# legatus_v0_21.net
KiCad netlist of a schematic drawn in EAGLE
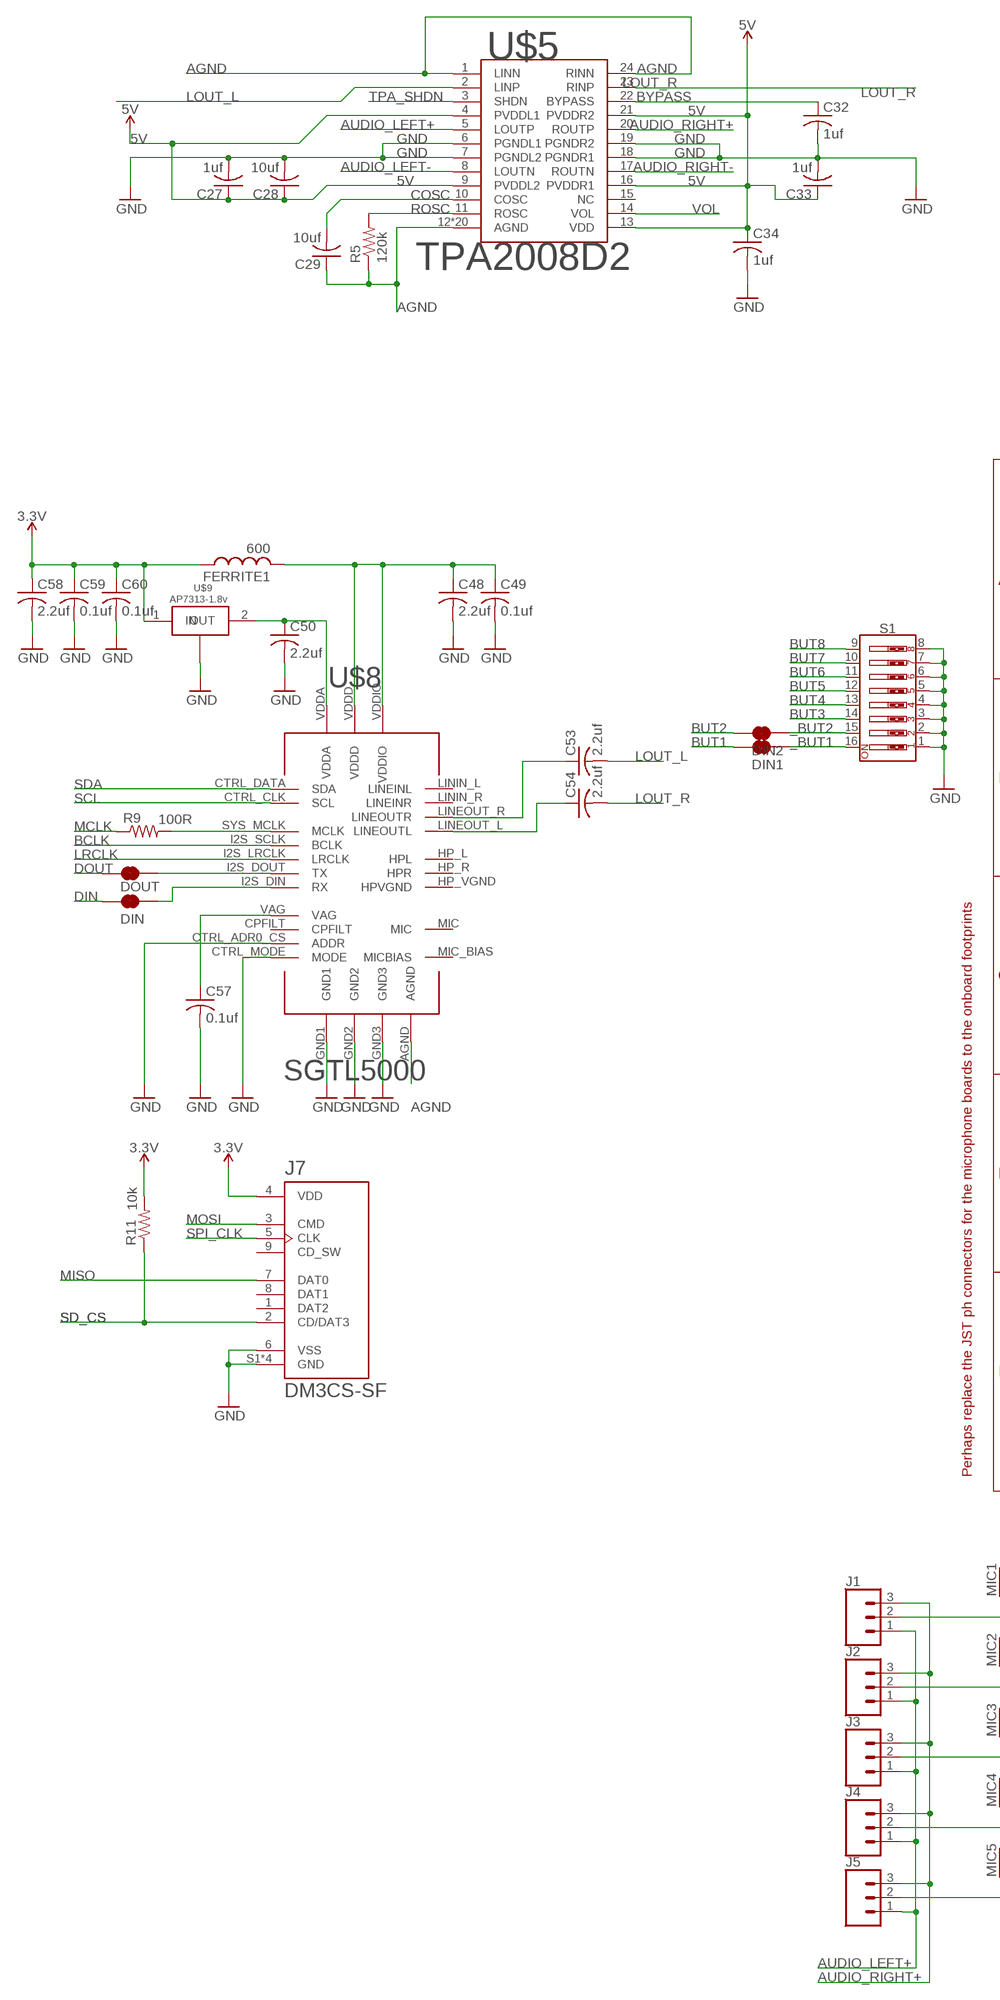
[diagram p0: schematic, sheet 1, part 1 of 2]
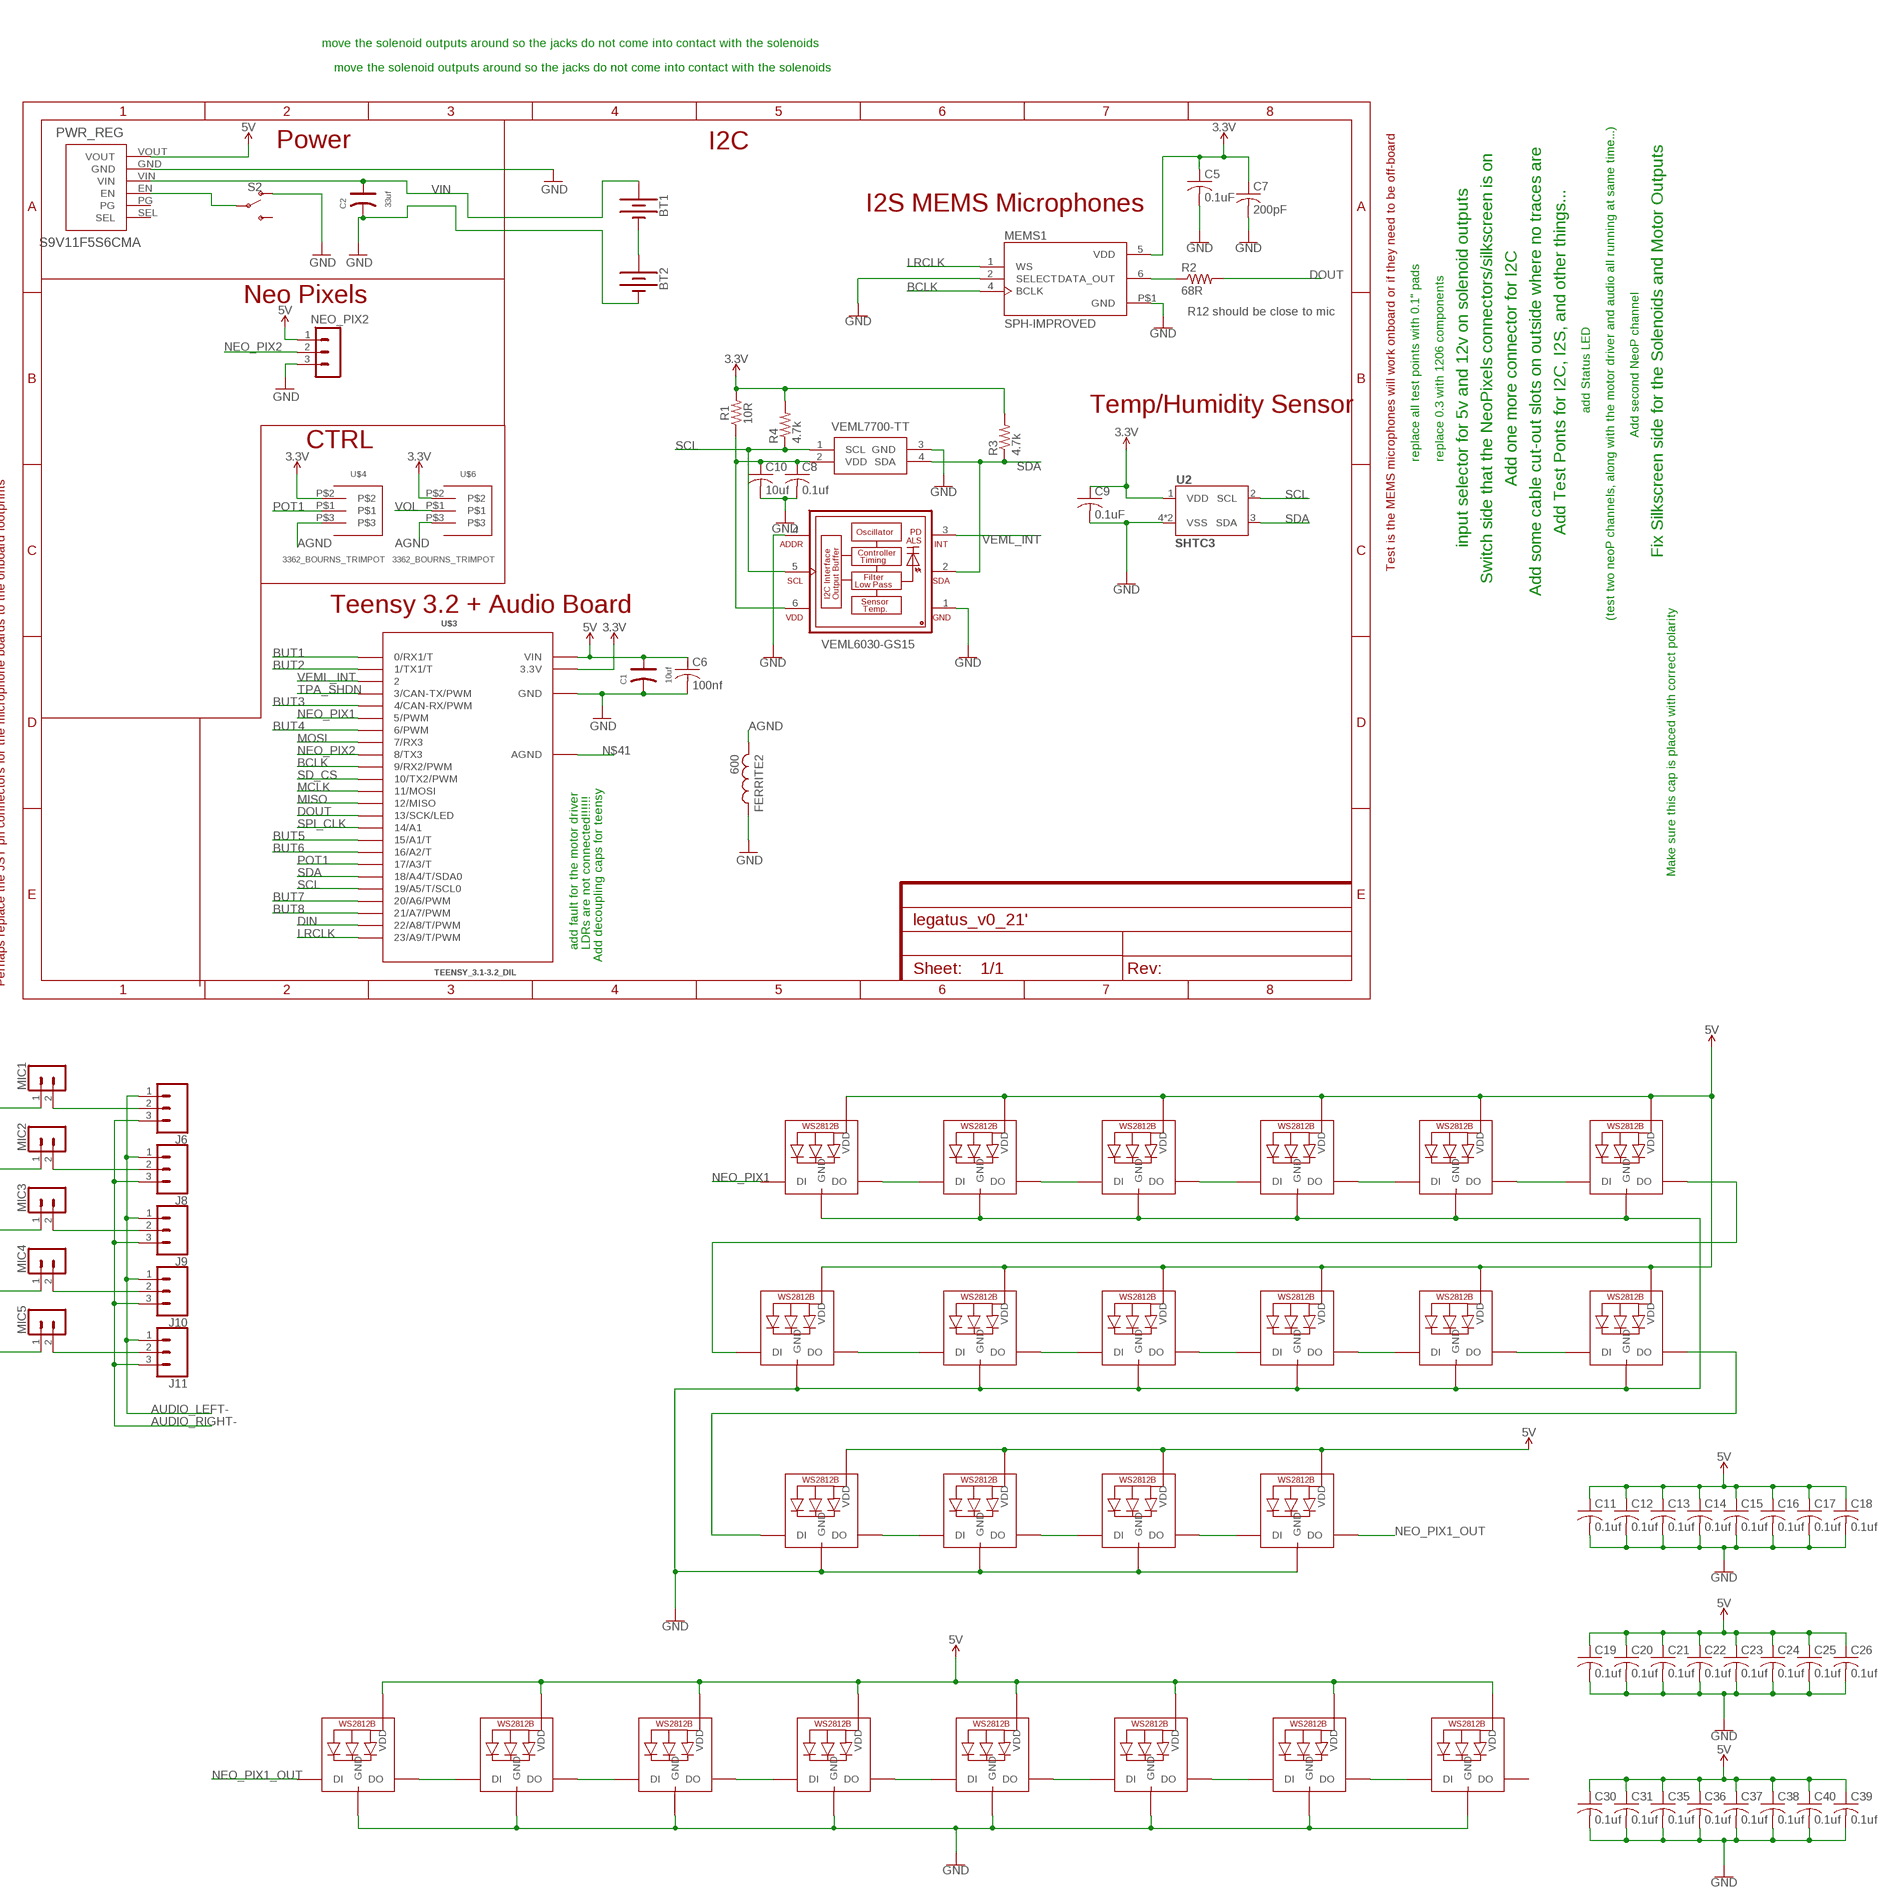
[diagram p1: schematic, sheet 1, part 2 of 2]

(export (version "E")
  (design (tool "Eeschema 10.0.6"))
  (components
    (comp (ref "BT1")
      (value "BATTERY-18650")
      (footprint "eagle-import:BATTERY_18650-HOLDER")
      (libsource (lib "eagle-import") (part "BATTERY-18650"))
    )
    (comp (ref "BT2")
      (value "BATTERY-18650")
      (footprint "eagle-import:BATTERY_18650-HOLDER")
      (libsource (lib "eagle-import") (part "BATTERY-18650"))
    )
    (comp (ref "C1")
      (value "10uf")
      (footprint "eagle-import:PC-D5.3MM")
      (fields (field (name "MPN") "KS 100uF/16V"))
      (libsource (lib "eagle-import") (part "DIP-ALUMINUM-47UF-16V(D5-H7MM)"))
    )
    (comp (ref "C2")
      (value "33uf")
      (footprint "eagle-import:PC-D5.3MM")
      (fields (field (name "MPN") "KS 100uF/16V"))
      (libsource (lib "eagle-import") (part "DIP-ALUMINUM-47UF-16V(D5-H7MM)"))
    )
    (comp (ref "C5")
      (value "0.1uF")
      (footprint "eagle-import:C0805")
      (libsource (lib "eagle-import") (part "rcl_334_C-USC0805"))
    )
    (comp (ref "C6")
      (value "100nf")
      (footprint "eagle-import:C2012")
      (libsource (lib "eagle-import") (part "C-USC2012"))
    )
    (comp (ref "C7")
      (value "200pF")
      (footprint "eagle-import:C0805")
      (libsource (lib "eagle-import") (part "rcl_334_C-USC0805"))
    )
    (comp (ref "C8")
      (value "0.1uf")
      (footprint "eagle-import:C0805")
      (libsource (lib "eagle-import") (part "rcl_334_C-USC0805"))
    )
    (comp (ref "C9")
      (value "0.1uF")
      (footprint "eagle-import:C0805")
      (libsource (lib "eagle-import") (part "rcl_334_C-USC0805"))
    )
    (comp (ref "C10")
      (value "10uf")
      (footprint "eagle-import:C0805")
      (libsource (lib "eagle-import") (part "rcl_334_C-USC0805"))
    )
    (comp (ref "C11")
      (value "0.1uf")
      (footprint "eagle-import:C0805")
      (libsource (lib "eagle-import") (part "rcl_334_C-USC0805"))
    )
    (comp (ref "C12")
      (value "0.1uf")
      (footprint "eagle-import:C0805")
      (libsource (lib "eagle-import") (part "rcl_334_C-USC0805"))
    )
    (comp (ref "C13")
      (value "0.1uf")
      (footprint "eagle-import:C0805")
      (libsource (lib "eagle-import") (part "rcl_334_C-USC0805"))
    )
    (comp (ref "C14")
      (value "0.1uf")
      (footprint "eagle-import:C0805")
      (libsource (lib "eagle-import") (part "rcl_334_C-USC0805"))
    )
    (comp (ref "C15")
      (value "0.1uf")
      (footprint "eagle-import:C0805")
      (libsource (lib "eagle-import") (part "rcl_334_C-USC0805"))
    )
    (comp (ref "C16")
      (value "0.1uf")
      (footprint "eagle-import:C0805")
      (libsource (lib "eagle-import") (part "rcl_334_C-USC0805"))
    )
    (comp (ref "C17")
      (value "0.1uf")
      (footprint "eagle-import:C0805")
      (libsource (lib "eagle-import") (part "rcl_334_C-USC0805"))
    )
    (comp (ref "C18")
      (value "0.1uf")
      (footprint "eagle-import:C0805")
      (libsource (lib "eagle-import") (part "rcl_334_C-USC0805"))
    )
    (comp (ref "C19")
      (value "0.1uf")
      (footprint "eagle-import:C0805")
      (libsource (lib "eagle-import") (part "rcl_334_C-USC0805"))
    )
    (comp (ref "C20")
      (value "0.1uf")
      (footprint "eagle-import:C0805")
      (libsource (lib "eagle-import") (part "rcl_334_C-USC0805"))
    )
    (comp (ref "C21")
      (value "0.1uf")
      (footprint "eagle-import:C0805")
      (libsource (lib "eagle-import") (part "rcl_334_C-USC0805"))
    )
    (comp (ref "C22")
      (value "0.1uf")
      (footprint "eagle-import:C0805")
      (libsource (lib "eagle-import") (part "rcl_334_C-USC0805"))
    )
    (comp (ref "C23")
      (value "0.1uf")
      (footprint "eagle-import:C0805")
      (libsource (lib "eagle-import") (part "rcl_334_C-USC0805"))
    )
    (comp (ref "C24")
      (value "0.1uf")
      (footprint "eagle-import:C0805")
      (libsource (lib "eagle-import") (part "rcl_334_C-USC0805"))
    )
    (comp (ref "C25")
      (value "0.1uf")
      (footprint "eagle-import:C0805")
      (libsource (lib "eagle-import") (part "rcl_334_C-USC0805"))
    )
    (comp (ref "C26")
      (value "0.1uf")
      (footprint "eagle-import:C0805")
      (libsource (lib "eagle-import") (part "rcl_334_C-USC0805"))
    )
    (comp (ref "C27")
      (value "1uf")
      (footprint "eagle-import:C0805")
      (libsource (lib "eagle-import") (part "rcl_334_C-USC0805"))
    )
    (comp (ref "C28")
      (value "10uf")
      (footprint "eagle-import:C0805")
      (libsource (lib "eagle-import") (part "rcl_334_C-USC0805"))
    )
    (comp (ref "C29")
      (value "10uf")
      (footprint "eagle-import:C0805")
      (libsource (lib "eagle-import") (part "rcl_334_C-USC0805"))
    )
    (comp (ref "C30")
      (value "0.1uf")
      (footprint "eagle-import:C0805")
      (libsource (lib "eagle-import") (part "rcl_334_C-USC0805"))
    )
    (comp (ref "C31")
      (value "0.1uf")
      (footprint "eagle-import:C0805")
      (libsource (lib "eagle-import") (part "rcl_334_C-USC0805"))
    )
    (comp (ref "C32")
      (value "1uf")
      (footprint "eagle-import:C0805")
      (libsource (lib "eagle-import") (part "rcl_334_C-USC0805"))
    )
    (comp (ref "C33")
      (value "1uf")
      (footprint "eagle-import:C0805")
      (libsource (lib "eagle-import") (part "rcl_334_C-USC0805"))
    )
    (comp (ref "C34")
      (value "1uf")
      (footprint "eagle-import:C0805")
      (libsource (lib "eagle-import") (part "rcl_334_C-USC0805"))
    )
    (comp (ref "C35")
      (value "0.1uf")
      (footprint "eagle-import:C0805")
      (libsource (lib "eagle-import") (part "rcl_334_C-USC0805"))
    )
    (comp (ref "C36")
      (value "0.1uf")
      (footprint "eagle-import:C0805")
      (libsource (lib "eagle-import") (part "rcl_334_C-USC0805"))
    )
    (comp (ref "C37")
      (value "0.1uf")
      (footprint "eagle-import:C0805")
      (libsource (lib "eagle-import") (part "rcl_334_C-USC0805"))
    )
    (comp (ref "C38")
      (value "0.1uf")
      (footprint "eagle-import:C0805")
      (libsource (lib "eagle-import") (part "rcl_334_C-USC0805"))
    )
    (comp (ref "C39")
      (value "0.1uf")
      (footprint "eagle-import:C0805")
      (libsource (lib "eagle-import") (part "rcl_334_C-USC0805"))
    )
    (comp (ref "C40")
      (value "0.1uf")
      (footprint "eagle-import:C0805")
      (libsource (lib "eagle-import") (part "rcl_334_C-USC0805"))
    )
    (comp (ref "C48")
      (value "2.2uf")
      (footprint "eagle-import:C0805")
      (libsource (lib "eagle-import") (part "rcl_334_C-USC0805"))
    )
    (comp (ref "C49")
      (value "0.1uf")
      (footprint "eagle-import:C0805")
      (libsource (lib "eagle-import") (part "rcl_334_C-USC0805"))
    )
    (comp (ref "C50")
      (value "2.2uf")
      (footprint "eagle-import:C0805")
      (libsource (lib "eagle-import") (part "rcl_334_C-USC0805"))
    )
    (comp (ref "C53")
      (value "2.2uf")
      (footprint "eagle-import:C0805")
      (libsource (lib "eagle-import") (part "rcl_334_C-USC0805"))
    )
    (comp (ref "C54")
      (value "2.2uf")
      (footprint "eagle-import:C0805")
      (libsource (lib "eagle-import") (part "rcl_334_C-USC0805"))
    )
    (comp (ref "C57")
      (value "0.1uf")
      (footprint "eagle-import:C0805")
      (libsource (lib "eagle-import") (part "rcl_334_C-USC0805"))
    )
    (comp (ref "C58")
      (value "2.2uf")
      (footprint "eagle-import:C0805")
      (libsource (lib "eagle-import") (part "rcl_334_C-USC0805"))
    )
    (comp (ref "C59")
      (value "0.1uf")
      (footprint "eagle-import:C0805")
      (libsource (lib "eagle-import") (part "rcl_334_C-USC0805"))
    )
    (comp (ref "C60")
      (value "0.1uf")
      (footprint "eagle-import:C0805")
      (libsource (lib "eagle-import") (part "rcl_334_C-USC0805"))
    )
    (comp (ref "DIN")
      (value "JUMPER-SMT_2_NC_TRACE_SILK")
      (footprint "eagle-import:SMT-JUMPER_2_NC_TRACE_SILK")
      (libsource (lib "eagle-import") (part "JUMPER-SMT_2_NC_TRACE_SILK"))
    )
    (comp (ref "DIN1")
      (value "JUMPER-SMT_2_NC_TRACE_SILK")
      (footprint "eagle-import:SMT-JUMPER_2_NC_TRACE_SILK")
      (libsource (lib "eagle-import") (part "JUMPER-SMT_2_NC_TRACE_SILK"))
    )
    (comp (ref "DIN2")
      (value "JUMPER-SMT_2_NC_TRACE_SILK")
      (footprint "eagle-import:SMT-JUMPER_2_NC_TRACE_SILK")
      (libsource (lib "eagle-import") (part "JUMPER-SMT_2_NC_TRACE_SILK"))
    )
    (comp (ref "DOUT")
      (value "JUMPER-SMT_2_NC_TRACE_SILK")
      (footprint "eagle-import:SMT-JUMPER_2_NC_TRACE_SILK")
      (libsource (lib "eagle-import") (part "JUMPER-SMT_2_NC_TRACE_SILK"))
    )
    (comp (ref "FERRITE1")
      (value "600")
      (footprint "eagle-import:RESC0805_N")
      (libsource (lib "eagle-import") (part "INDUCTOR_0805_N"))
    )
    (comp (ref "FERRITE2")
      (value "600")
      (footprint "eagle-import:RESC0805_N")
      (libsource (lib "eagle-import") (part "INDUCTOR_0805_N"))
    )
    (comp (ref "J1")
      (value "CONN_03")
      (footprint "eagle-import:1X03")
      (libsource (lib "eagle-import") (part "CONN_03"))
    )
    (comp (ref "J2")
      (value "CONN_03")
      (footprint "eagle-import:1X03")
      (libsource (lib "eagle-import") (part "CONN_03"))
    )
    (comp (ref "J3")
      (value "CONN_03")
      (footprint "eagle-import:1X03")
      (libsource (lib "eagle-import") (part "CONN_03"))
    )
    (comp (ref "J4")
      (value "CONN_03")
      (footprint "eagle-import:1X03")
      (libsource (lib "eagle-import") (part "CONN_03"))
    )
    (comp (ref "J5")
      (value "CONN_03")
      (footprint "eagle-import:1X03")
      (libsource (lib "eagle-import") (part "CONN_03"))
    )
    (comp (ref "J6")
      (value "CONN_03")
      (footprint "eagle-import:1X03")
      (libsource (lib "eagle-import") (part "CONN_03"))
    )
    (comp (ref "J7")
      (value "DM3CS-SF")
      (footprint "eagle-import:HRS_DM3CS-SF")
      (fields (field (name "MF") "Hirose"))
      (libsource (lib "eagle-import") (part "DM3CS-SF"))
    )
    (comp (ref "J8")
      (value "CONN_03")
      (footprint "eagle-import:1X03")
      (libsource (lib "eagle-import") (part "CONN_03"))
    )
    (comp (ref "J9")
      (value "CONN_03")
      (footprint "eagle-import:1X03")
      (libsource (lib "eagle-import") (part "CONN_03"))
    )
    (comp (ref "J10")
      (value "CONN_03")
      (footprint "eagle-import:1X03")
      (libsource (lib "eagle-import") (part "CONN_03"))
    )
    (comp (ref "J11")
      (value "CONN_03")
      (footprint "eagle-import:1X03")
      (libsource (lib "eagle-import") (part "CONN_03"))
    )
    (comp (ref "LED1")
      (value "WS2812B_5050N")
      (footprint "eagle-import:WS2812B-NARROW")
      (libsource (lib "eagle-import") (part "WS2812B_5050N"))
    )
    (comp (ref "LED2")
      (value "WS2812B_5050N")
      (footprint "eagle-import:WS2812B-NARROW")
      (libsource (lib "eagle-import") (part "WS2812B_5050N"))
    )
    (comp (ref "LED3")
      (value "WS2812B_5050N")
      (footprint "eagle-import:WS2812B-NARROW")
      (libsource (lib "eagle-import") (part "WS2812B_5050N"))
    )
    (comp (ref "LED4")
      (value "WS2812B_5050N")
      (footprint "eagle-import:WS2812B-NARROW")
      (libsource (lib "eagle-import") (part "WS2812B_5050N"))
    )
    (comp (ref "LED5")
      (value "WS2812B_5050N")
      (footprint "eagle-import:WS2812B-NARROW")
      (libsource (lib "eagle-import") (part "WS2812B_5050N"))
    )
    (comp (ref "LED6")
      (value "WS2812B_5050N")
      (footprint "eagle-import:WS2812B-NARROW")
      (libsource (lib "eagle-import") (part "WS2812B_5050N"))
    )
    (comp (ref "LED7")
      (value "WS2812B_5050N")
      (footprint "eagle-import:WS2812B-NARROW")
      (libsource (lib "eagle-import") (part "WS2812B_5050N"))
    )
    (comp (ref "LED8")
      (value "WS2812B_5050N")
      (footprint "eagle-import:WS2812B-NARROW")
      (libsource (lib "eagle-import") (part "WS2812B_5050N"))
    )
    (comp (ref "LED9")
      (value "WS2812B_5050N")
      (footprint "eagle-import:WS2812B-NARROW")
      (libsource (lib "eagle-import") (part "WS2812B_5050N"))
    )
    (comp (ref "LED10")
      (value "WS2812B_5050N")
      (footprint "eagle-import:WS2812B-NARROW")
      (libsource (lib "eagle-import") (part "WS2812B_5050N"))
    )
    (comp (ref "LED11")
      (value "WS2812B_5050N")
      (footprint "eagle-import:WS2812B-NARROW")
      (libsource (lib "eagle-import") (part "WS2812B_5050N"))
    )
    (comp (ref "LED12")
      (value "WS2812B_5050N")
      (footprint "eagle-import:WS2812B-NARROW")
      (libsource (lib "eagle-import") (part "WS2812B_5050N"))
    )
    (comp (ref "LED13")
      (value "WS2812B_5050N")
      (footprint "eagle-import:WS2812B-NARROW")
      (libsource (lib "eagle-import") (part "WS2812B_5050N"))
    )
    (comp (ref "LED14")
      (value "WS2812B_5050N")
      (footprint "eagle-import:WS2812B-NARROW")
      (libsource (lib "eagle-import") (part "WS2812B_5050N"))
    )
    (comp (ref "LED15")
      (value "WS2812B_5050N")
      (footprint "eagle-import:WS2812B-NARROW")
      (libsource (lib "eagle-import") (part "WS2812B_5050N"))
    )
    (comp (ref "LED16")
      (value "WS2812B_5050N")
      (footprint "eagle-import:WS2812B-NARROW")
      (libsource (lib "eagle-import") (part "WS2812B_5050N"))
    )
    (comp (ref "LED17")
      (value "WS2812B_5050N")
      (footprint "eagle-import:WS2812B-NARROW")
      (libsource (lib "eagle-import") (part "WS2812B_5050N"))
    )
    (comp (ref "LED18")
      (value "WS2812B_5050N")
      (footprint "eagle-import:WS2812B-NARROW")
      (libsource (lib "eagle-import") (part "WS2812B_5050N"))
    )
    (comp (ref "LED19")
      (value "WS2812B_5050N")
      (footprint "eagle-import:WS2812B-NARROW")
      (libsource (lib "eagle-import") (part "WS2812B_5050N"))
    )
    (comp (ref "LED20")
      (value "WS2812B_5050N")
      (footprint "eagle-import:WS2812B-NARROW")
      (libsource (lib "eagle-import") (part "WS2812B_5050N"))
    )
    (comp (ref "LED21")
      (value "WS2812B_5050N")
      (footprint "eagle-import:WS2812B-NARROW")
      (libsource (lib "eagle-import") (part "WS2812B_5050N"))
    )
    (comp (ref "LED22")
      (value "WS2812B_5050N")
      (footprint "eagle-import:WS2812B-NARROW")
      (libsource (lib "eagle-import") (part "WS2812B_5050N"))
    )
    (comp (ref "LED23")
      (value "WS2812B_5050N")
      (footprint "eagle-import:WS2812B-NARROW")
      (libsource (lib "eagle-import") (part "WS2812B_5050N"))
    )
    (comp (ref "LED24")
      (value "WS2812B_5050N")
      (footprint "eagle-import:WS2812B-NARROW")
      (libsource (lib "eagle-import") (part "WS2812B_5050N"))
    )
    (comp (ref "MEMS1")
      (value "SPH-IMPROVED")
      (footprint "eagle-import:MIC_SPH0645LM4H-B_LARGER_RING")
      (libsource (lib "eagle-import") (part "SPH-IMPROVED"))
    )
    (comp (ref "MIC1")
      (value "B2B-PH-K")
      (footprint "eagle-import:B2B-PH-K")
      (libsource (lib "eagle-import") (part "B2B-PH-K"))
    )
    (comp (ref "MIC2")
      (value "B2B-PH-K")
      (footprint "eagle-import:B2B-PH-K")
      (libsource (lib "eagle-import") (part "B2B-PH-K"))
    )
    (comp (ref "MIC3")
      (value "B2B-PH-K")
      (footprint "eagle-import:B2B-PH-K")
      (libsource (lib "eagle-import") (part "B2B-PH-K"))
    )
    (comp (ref "MIC4")
      (value "B2B-PH-K")
      (footprint "eagle-import:B2B-PH-K")
      (libsource (lib "eagle-import") (part "B2B-PH-K"))
    )
    (comp (ref "MIC5")
      (value "B2B-PH-K")
      (footprint "eagle-import:B2B-PH-K")
      (libsource (lib "eagle-import") (part "B2B-PH-K"))
    )
    (comp (ref "NEO_PIX2")
      (value "B3B-PH-K")
      (footprint "eagle-import:B3B-PH-K")
      (libsource (lib "eagle-import") (part "B3B-PH-K"))
    )
    (comp (ref "PWR_REG")
      (value "S9V11F5S6CMA")
      (footprint "eagle-import:S9V11F3S5CMA")
      (libsource (lib "eagle-import") (part "S9V11F5S6CMA"))
    )
    (comp (ref "R1")
      (value "10R")
      (footprint "eagle-import:R0805")
      (libsource (lib "eagle-import") (part "audio amplifier example_970892_R-US_R0805"))
    )
    (comp (ref "R2")
      (value "68R")
      (footprint "eagle-import:M0805")
      (libsource (lib "eagle-import") (part "R-US_M0805"))
    )
    (comp (ref "R3")
      (value "4.7k")
      (footprint "eagle-import:M0805")
      (libsource (lib "eagle-import") (part "R-US_M0805"))
    )
    (comp (ref "R4")
      (value "4.7k")
      (footprint "eagle-import:M0805")
      (libsource (lib "eagle-import") (part "R-US_M0805"))
    )
    (comp (ref "R5")
      (value "120k")
      (footprint "eagle-import:M0805")
      (libsource (lib "eagle-import") (part "R-US_M0805"))
    )
    (comp (ref "R9")
      (value "100R")
      (footprint "eagle-import:M0805")
      (libsource (lib "eagle-import") (part "rcl_R-US_M0805"))
    )
    (comp (ref "R11")
      (value "10k")
      (footprint "eagle-import:M0805")
      (libsource (lib "eagle-import") (part "rcl_R-US_M0805"))
    )
    (comp (ref "S1")
      (value "DIP-08-PTH")
      (footprint "eagle-import:DIPSWITCH-08")
      (libsource (lib "eagle-import") (part "DIP-08-PTH"))
    )
    (comp (ref "S2")
      (value "SWITCH-SPDT-PTH-11.6X4.0MM-LOCK")
      (footprint "eagle-import:SWITCH_SPDT_PTH_11.6X4.0MM_LOCK")
      (libsource (lib "eagle-import") (part "SWITCH-SPDT-PTH-11.6X4.0MM-LOCK"))
    )
    (comp (ref "U$3")
      (value "TEENSY_3.1-3.2_DIL")
      (footprint "eagle-import:TEENSY_3.0-3.2&LC_DIL")
      (libsource (lib "eagle-import") (part "TEENSY_3.1-3.2_DIL"))
    )
    (comp (ref "U$4")
      (value "3362_BOURNS_TRIMPOT")
      (footprint "eagle-import:3362_BOURNS_TRIMPOT")
      (libsource (lib "eagle-import") (part "3362_BOURNS_TRIMPOT"))
    )
    (comp (ref "U$5")
      (value "TPA2008D2")
      (footprint "eagle-import:PWP-TSSOP24")
      (libsource (lib "eagle-import") (part "TPA2008D2"))
    )
    (comp (ref "U$6")
      (value "3362_BOURNS_TRIMPOT")
      (footprint "eagle-import:3362_BOURNS_TRIMPOT")
      (libsource (lib "eagle-import") (part "3362_BOURNS_TRIMPOT"))
    )
    (comp (ref "U$8")
      (value "SGTL5000")
      (footprint "eagle-import:QFN-32-5X5MM")
      (libsource (lib "eagle-import") (part "SGTL5000"))
    )
    (comp (ref "U$9")
      (value "AP7313-1.8v")
      (footprint "eagle-import:SOT-23")
      (libsource (lib "eagle-import") (part "AP7313"))
    )
    (comp (ref "U2")
      (value "SHTC3")
      (footprint "eagle-import:SHTC3")
      (libsource (lib "eagle-import") (part "SHTC3"))
    )
    (comp (ref "VEML1")
      (value "VEML7700-TT")
      (footprint "eagle-import:VEML7700")
      (fields (field (name "MOUSER_PART_NUMBER") "78-VEML7700-TT") (field (name "RS_PART_NUMBER") "1226791P"))
      (libsource (lib "eagle-import") (part "VEML7700-TT"))
    )
    (comp (ref "VMEL1")
      (value "VEML6030-GS15")
      (footprint "eagle-import:VISHAY_VEML6030_2X2X0.87")
      (fields (field (name "MF") "Vishay Semiconductor"))
      (libsource (lib "eagle-import") (part "VEML6030-GS15"))
    )
  )
  (nets
    (net (code "1") (name "/AGND") (class "Default")
      (node (ref "C29") (pin "1") (pinfunction "1_1") (pintype "passive"))
      (node (ref "FERRITE2") (pin "2") (pinfunction "2_2") (pintype "passive"))
      (node (ref "R5") (pin "1") (pinfunction "1_1") (pintype "passive"))
      (node (ref "U$4") (pin "P$3") (pinfunction "P$3_P$3") (pintype "bidirectional"))
      (node (ref "U$5") (pin "1") (pinfunction "LINN_1") (pintype "bidirectional"))
      (node (ref "U$5") (pin "12") (pinfunction "AGND_12") (pintype "bidirectional"))
      (node (ref "U$5") (pin "24") (pinfunction "RINN_24") (pintype "bidirectional"))
      (node (ref "U$5") (pin "EXP") (pinfunction "AGND_EXP") (pintype "bidirectional"))
      (node (ref "U$5") (pin "EXP@1") (pinfunction "AGND_EXP@1") (pintype "bidirectional"))
      (node (ref "U$5") (pin "EXP@10") (pinfunction "AGND_EXP@10") (pintype "bidirectional"))
      (node (ref "U$5") (pin "EXP@11") (pinfunction "AGND_EXP@11") (pintype "bidirectional"))
      (node (ref "U$5") (pin "EXP@12") (pinfunction "AGND_EXP@12") (pintype "bidirectional"))
      (node (ref "U$5") (pin "EXP@13") (pinfunction "AGND_EXP@13") (pintype "bidirectional"))
      (node (ref "U$5") (pin "EXP@14") (pinfunction "AGND_EXP@14") (pintype "bidirectional"))
      (node (ref "U$5") (pin "EXP@15") (pinfunction "AGND_EXP@15") (pintype "bidirectional"))
      (node (ref "U$5") (pin "EXP@16") (pinfunction "AGND_EXP@16") (pintype "bidirectional"))
      (node (ref "U$5") (pin "EXP@17") (pinfunction "AGND_EXP@17") (pintype "bidirectional"))
      (node (ref "U$5") (pin "EXP@18") (pinfunction "AGND_EXP@18") (pintype "bidirectional"))
      (node (ref "U$5") (pin "EXP@2") (pinfunction "AGND_EXP@2") (pintype "bidirectional"))
      (node (ref "U$5") (pin "EXP@3") (pinfunction "AGND_EXP@3") (pintype "bidirectional"))
      (node (ref "U$5") (pin "EXP@4") (pinfunction "AGND_EXP@4") (pintype "bidirectional"))
      (node (ref "U$5") (pin "EXP@5") (pinfunction "AGND_EXP@5") (pintype "bidirectional"))
      (node (ref "U$5") (pin "EXP@6") (pinfunction "AGND_EXP@6") (pintype "bidirectional"))
      (node (ref "U$5") (pin "EXP@7") (pinfunction "AGND_EXP@7") (pintype "bidirectional"))
      (node (ref "U$5") (pin "EXP@8") (pinfunction "AGND_EXP@8") (pintype "bidirectional"))
      (node (ref "U$5") (pin "EXP@9") (pinfunction "AGND_EXP@9") (pintype "bidirectional"))
      (node (ref "U$6") (pin "P$3") (pinfunction "P$3_P$3") (pintype "bidirectional"))
      (node (ref "U$8") (pin "AGND") (pinfunction "AGND_AGND") (pintype "bidirectional"))
    )
    (net (code "2") (name "/AUDIO_LEFT+") (class "Default")
      (node (ref "J1") (pin "1") (pinfunction "1_1") (pintype "passive"))
      (node (ref "J2") (pin "1") (pinfunction "1_1") (pintype "passive"))
      (node (ref "J3") (pin "1") (pinfunction "1_1") (pintype "passive"))
      (node (ref "J4") (pin "1") (pinfunction "1_1") (pintype "passive"))
      (node (ref "J5") (pin "1") (pinfunction "1_1") (pintype "passive"))
      (node (ref "U$5") (pin "5") (pinfunction "LOUTP_5") (pintype "bidirectional"))
    )
    (net (code "3") (name "/AUDIO_LEFT-") (class "Default")
      (node (ref "J10") (pin "1") (pinfunction "1_1") (pintype "passive"))
      (node (ref "J11") (pin "1") (pinfunction "1_1") (pintype "passive"))
      (node (ref "J6") (pin "1") (pinfunction "1_1") (pintype "passive"))
      (node (ref "J8") (pin "1") (pinfunction "1_1") (pintype "passive"))
      (node (ref "J9") (pin "1") (pinfunction "1_1") (pintype "passive"))
      (node (ref "U$5") (pin "8") (pinfunction "LOUTN_8") (pintype "bidirectional"))
    )
    (net (code "4") (name "/AUDIO_RIGHT+") (class "Default")
      (node (ref "J1") (pin "3") (pinfunction "3_3") (pintype "passive"))
      (node (ref "J2") (pin "3") (pinfunction "3_3") (pintype "passive"))
      (node (ref "J3") (pin "3") (pinfunction "3_3") (pintype "passive"))
      (node (ref "J4") (pin "3") (pinfunction "3_3") (pintype "passive"))
      (node (ref "J5") (pin "3") (pinfunction "3_3") (pintype "passive"))
      (node (ref "U$5") (pin "20") (pinfunction "ROUTP_20") (pintype "bidirectional"))
    )
    (net (code "5") (name "/AUDIO_RIGHT-") (class "Default")
      (node (ref "J10") (pin "3") (pinfunction "3_3") (pintype "passive"))
      (node (ref "J11") (pin "3") (pinfunction "3_3") (pintype "passive"))
      (node (ref "J6") (pin "3") (pinfunction "3_3") (pintype "passive"))
      (node (ref "J8") (pin "3") (pinfunction "3_3") (pintype "passive"))
      (node (ref "J9") (pin "3") (pinfunction "3_3") (pintype "passive"))
      (node (ref "U$5") (pin "17") (pinfunction "ROUTN_17") (pintype "bidirectional"))
    )
    (net (code "6") (name "/BCLK") (class "Default")
      (node (ref "MEMS1") (pin "4") (pinfunction "BCLK_4") (pintype "input"))
      (node (ref "U$3") (pin "9") (pinfunction "9/RX2/PWM_9") (pintype "bidirectional"))
      (node (ref "U$8") (pin "I2S_SCLK") (pinfunction "BCLK_I2S_SCLK") (pintype "bidirectional"))
    )
    (net (code "7") (name "/BUT1") (class "Default")
      (node (ref "DIN1") (pin "1") (pinfunction "1_1") (pintype "passive"))
      (node (ref "U$3") (pin "0") (pinfunction "0/RX1/T_0") (pintype "bidirectional"))
    )
    (net (code "8") (name "/BUT2") (class "Default")
      (node (ref "DIN2") (pin "1") (pinfunction "1_1") (pintype "passive"))
      (node (ref "U$3") (pin "1") (pinfunction "1/TX1/T_1") (pintype "bidirectional"))
    )
    (net (code "9") (name "/BUT3") (class "Default")
      (node (ref "S1") (pin "14") (pinfunction "14_14") (pintype "passive"))
      (node (ref "U$3") (pin "4") (pinfunction "4/CAN-RX/PWM_4") (pintype "bidirectional"))
    )
    (net (code "10") (name "/BUT4") (class "Default")
      (node (ref "S1") (pin "13") (pinfunction "13_13") (pintype "passive"))
      (node (ref "U$3") (pin "6") (pinfunction "6/PWM_6") (pintype "bidirectional"))
    )
    (net (code "11") (name "/BUT5") (class "Default")
      (node (ref "S1") (pin "12") (pinfunction "12_12") (pintype "passive"))
      (node (ref "U$3") (pin "15/A1") (pinfunction "15/A1/T_15/A1") (pintype "bidirectional"))
    )
    (net (code "12") (name "/BUT6") (class "Default")
      (node (ref "S1") (pin "11") (pinfunction "11_11") (pintype "passive"))
      (node (ref "U$3") (pin "16/A2") (pinfunction "16/A2/T_16/A2") (pintype "bidirectional"))
    )
    (net (code "13") (name "/BUT7") (class "Default")
      (node (ref "S1") (pin "10") (pinfunction "10_10") (pintype "passive"))
      (node (ref "U$3") (pin "20/A6") (pinfunction "20/A6/PWM_20/A6") (pintype "bidirectional"))
    )
    (net (code "14") (name "/BUT8") (class "Default")
      (node (ref "S1") (pin "9") (pinfunction "9_9") (pintype "passive"))
      (node (ref "U$3") (pin "21/A7") (pinfunction "21/A7/PWM_21/A7") (pintype "bidirectional"))
    )
    (net (code "15") (name "/BYPASS") (class "Default")
      (node (ref "C32") (pin "1") (pinfunction "1_1") (pintype "passive"))
      (node (ref "U$5") (pin "22") (pinfunction "BYPASS_22") (pintype "bidirectional"))
    )
    (net (code "16") (name "/COSC") (class "Default")
      (node (ref "C29") (pin "2") (pinfunction "2_2") (pintype "passive"))
      (node (ref "U$5") (pin "10") (pinfunction "COSC_10") (pintype "bidirectional"))
    )
    (net (code "17") (name "/DIN") (class "Default")
      (node (ref "DIN") (pin "1") (pinfunction "1_1") (pintype "passive"))
      (node (ref "U$3") (pin "22/A8") (pinfunction "22/A8/T/PWM_22/A8") (pintype "bidirectional"))
    )
    (net (code "18") (name "/DOUT") (class "Default")
      (node (ref "DOUT") (pin "1") (pinfunction "1_1") (pintype "passive"))
      (node (ref "R2") (pin "2") (pinfunction "2_2") (pintype "passive"))
      (node (ref "U$3") (pin "13") (pinfunction "13/SCK/LED_13") (pintype "bidirectional"))
    )
    (net (code "19") (name "/LOUT_L") (class "Default")
      (node (ref "C53") (pin "2") (pinfunction "2_2") (pintype "passive"))
      (node (ref "U$5") (pin "2") (pinfunction "LINP_2") (pintype "bidirectional"))
    )
    (net (code "20") (name "/LOUT_R") (class "Default")
      (node (ref "C54") (pin "2") (pinfunction "2_2") (pintype "passive"))
      (node (ref "U$5") (pin "23") (pinfunction "RINP_23") (pintype "bidirectional"))
    )
    (net (code "21") (name "/LRCLK") (class "Default")
      (node (ref "MEMS1") (pin "1") (pinfunction "WS_1") (pintype "input"))
      (node (ref "U$3") (pin "23/A9") (pinfunction "23/A9/T/PWM_23/A9") (pintype "bidirectional"))
      (node (ref "U$8") (pin "I2S_LRCLK") (pinfunction "LRCLK_I2S_LRCLK") (pintype "bidirectional"))
    )
    (net (code "22") (name "/MCLK") (class "Default")
      (node (ref "R9") (pin "1") (pinfunction "1_1") (pintype "passive"))
      (node (ref "U$3") (pin "11") (pinfunction "11/MOSI_11") (pintype "bidirectional"))
    )
    (net (code "23") (name "/MISO") (class "Default")
      (node (ref "J7") (pin "7") (pinfunction "DAT0_7") (pintype "passive"))
      (node (ref "U$3") (pin "12") (pinfunction "12/MISO_12") (pintype "bidirectional"))
    )
    (net (code "24") (name "/MOSI") (class "Default")
      (node (ref "J7") (pin "3") (pinfunction "CMD_3") (pintype "passive"))
      (node (ref "U$3") (pin "7") (pinfunction "7/RX3_7") (pintype "bidirectional"))
    )
    (net (code "25") (name "/N$41") (class "Default")
      (node (ref "U$3") (pin "AGND") (pinfunction "AGND_AGND") (pintype "power_in"))
    )
    (net (code "26") (name "/NEO_PIX1") (class "Default")
      (node (ref "LED1") (pin "4-DIN") (pinfunction "DI_4-DIN") (pintype "input"))
      (node (ref "U$3") (pin "5") (pinfunction "5/PWM_5") (pintype "bidirectional"))
    )
    (net (code "27") (name "/NEO_PIX1_OUT") (class "Default")
      (node (ref "LED16") (pin "2-DOUT") (pinfunction "DO_2-DOUT") (pintype "output"))
      (node (ref "LED17") (pin "4-DIN") (pinfunction "DI_4-DIN") (pintype "input"))
    )
    (net (code "28") (name "/NEO_PIX2") (class "Default")
      (node (ref "NEO_PIX2") (pin "2") (pinfunction "2_2") (pintype "passive"))
      (node (ref "U$3") (pin "8") (pinfunction "8/TX3_8") (pintype "bidirectional"))
    )
    (net (code "29") (name "/POT1") (class "Default")
      (node (ref "U$3") (pin "17/A3") (pinfunction "17/A3/T_17/A3") (pintype "bidirectional"))
      (node (ref "U$4") (pin "P$1") (pinfunction "P$1_P$1") (pintype "bidirectional"))
    )
    (net (code "30") (name "/ROSC") (class "Default")
      (node (ref "R5") (pin "2") (pinfunction "2_2") (pintype "passive"))
      (node (ref "U$5") (pin "11") (pinfunction "ROSC_11") (pintype "bidirectional"))
    )
    (net (code "31") (name "/SCL") (class "Default")
      (node (ref "R4") (pin "1") (pinfunction "1_1") (pintype "passive"))
      (node (ref "U$3") (pin "19/A5") (pinfunction "19/A5/T/SCL0_19/A5") (pintype "bidirectional"))
      (node (ref "U$8") (pin "CTRL_CLK") (pinfunction "SCL_CTRL_CLK") (pintype "bidirectional"))
      (node (ref "U2") (pin "2") (pinfunction "SCL_2") (pintype "bidirectional"))
      (node (ref "VEML1") (pin "1") (pinfunction "SCL_1") (pintype "bidirectional"))
      (node (ref "VMEL1") (pin "5") (pinfunction "SCL_5") (pintype "input"))
    )
    (net (code "32") (name "/SDA") (class "Default")
      (node (ref "R3") (pin "1") (pinfunction "1_1") (pintype "passive"))
      (node (ref "U$3") (pin "18/A4") (pinfunction "18/A4/T/SDA0_18/A4") (pintype "bidirectional"))
      (node (ref "U$8") (pin "CTRL_DATA") (pinfunction "SDA_CTRL_DATA") (pintype "bidirectional"))
      (node (ref "U2") (pin "3") (pinfunction "SDA_3") (pintype "bidirectional"))
      (node (ref "VEML1") (pin "4") (pinfunction "SDA_4") (pintype "bidirectional"))
      (node (ref "VMEL1") (pin "2") (pinfunction "SDA_2") (pintype "bidirectional"))
    )
    (net (code "33") (name "/SD_CS") (class "Default")
      (node (ref "J7") (pin "2") (pinfunction "CD/DAT3_2") (pintype "passive"))
      (node (ref "R11") (pin "1") (pinfunction "1_1") (pintype "passive"))
      (node (ref "U$3") (pin "10") (pinfunction "10/TX2/PWM_10") (pintype "bidirectional"))
    )
    (net (code "34") (name "/SPI_CLK") (class "Default")
      (node (ref "J7") (pin "5") (pinfunction "CLK_5") (pintype "passive"))
      (node (ref "U$3") (pin "14/A0") (pinfunction "14/A1_14/A0") (pintype "bidirectional"))
    )
    (net (code "35") (name "/TPA_SHDN") (class "Default")
      (node (ref "U$3") (pin "3") (pinfunction "3/CAN-TX/PWM_3") (pintype "bidirectional"))
      (node (ref "U$5") (pin "3") (pinfunction "SHDN_3") (pintype "bidirectional"))
    )
    (net (code "36") (name "/VEML_INT") (class "Default")
      (node (ref "U$3") (pin "2") (pinfunction "2_2") (pintype "bidirectional"))
      (node (ref "VMEL1") (pin "3") (pinfunction "INT_3") (pintype "output"))
    )
    (net (code "37") (name "/VIN") (class "Default")
      (node (ref "BT1") (pin "PWR@1") (pinfunction "+_PWR@1") (pintype "power_in"))
      (node (ref "C2") (pin "+") (pinfunction "+_+") (pintype "passive"))
      (node (ref "PWR_REG") (pin "VIN") (pinfunction "VIN_VIN") (pintype "bidirectional"))
    )
    (net (code "38") (name "/VOL") (class "Default")
      (node (ref "U$5") (pin "14") (pinfunction "VOL_14") (pintype "bidirectional"))
      (node (ref "U$6") (pin "P$1") (pinfunction "P$1_P$1") (pintype "bidirectional"))
    )
    (net (code "39") (name "/_BUT1") (class "Default")
      (node (ref "DIN1") (pin "2") (pinfunction "2_2") (pintype "passive"))
      (node (ref "S1") (pin "16") (pinfunction "16_16") (pintype "passive"))
    )
    (net (code "40") (name "/_BUT2") (class "Default")
      (node (ref "DIN2") (pin "2") (pinfunction "2_2") (pintype "passive"))
      (node (ref "S1") (pin "15") (pinfunction "15_15") (pintype "passive"))
    )
    (net (code "41") (name "3.3V") (class "Default")
      (node (ref "C5") (pin "1") (pinfunction "1_1") (pintype "passive"))
      (node (ref "C58") (pin "1") (pinfunction "1_1") (pintype "passive"))
      (node (ref "C59") (pin "1") (pinfunction "1_1") (pintype "passive"))
      (node (ref "C60") (pin "1") (pinfunction "1_1") (pintype "passive"))
      (node (ref "C7") (pin "1") (pinfunction "1_1") (pintype "passive"))
      (node (ref "C9") (pin "1") (pinfunction "1_1") (pintype "passive"))
      (node (ref "FERRITE1") (pin "1") (pinfunction "1_1") (pintype "passive"))
      (node (ref "J7") (pin "4") (pinfunction "VDD_4") (pintype "passive"))
      (node (ref "MEMS1") (pin "5") (pinfunction "VDD_5") (pintype "power_in"))
      (node (ref "R1") (pin "2") (pinfunction "2_2") (pintype "passive"))
      (node (ref "R11") (pin "2") (pinfunction "2_2") (pintype "passive"))
      (node (ref "R3") (pin "2") (pinfunction "2_2") (pintype "passive"))
      (node (ref "R4") (pin "2") (pinfunction "2_2") (pintype "passive"))
      (node (ref "U$3") (pin "3.3V") (pinfunction "3.3V_3.3V") (pintype "power_in"))
      (node (ref "U$4") (pin "P$2") (pinfunction "P$2_P$2") (pintype "bidirectional"))
      (node (ref "U$6") (pin "P$2") (pinfunction "P$2_P$2") (pintype "bidirectional"))
      (node (ref "U$9") (pin "1") (pinfunction "IN_1") (pintype "bidirectional"))
      (node (ref "U2") (pin "1") (pinfunction "VDD_1") (pintype "bidirectional"))
    )
    (net (code "42") (name "5V") (class "Default")
      (node (ref "C1") (pin "+") (pinfunction "+_+") (pintype "passive"))
      (node (ref "C11") (pin "1") (pinfunction "1_1") (pintype "passive"))
      (node (ref "C12") (pin "1") (pinfunction "1_1") (pintype "passive"))
      (node (ref "C13") (pin "1") (pinfunction "1_1") (pintype "passive"))
      (node (ref "C14") (pin "1") (pinfunction "1_1") (pintype "passive"))
      (node (ref "C15") (pin "1") (pinfunction "1_1") (pintype "passive"))
      (node (ref "C16") (pin "1") (pinfunction "1_1") (pintype "passive"))
      (node (ref "C17") (pin "1") (pinfunction "1_1") (pintype "passive"))
      (node (ref "C18") (pin "1") (pinfunction "1_1") (pintype "passive"))
      (node (ref "C19") (pin "1") (pinfunction "1_1") (pintype "passive"))
      (node (ref "C20") (pin "1") (pinfunction "1_1") (pintype "passive"))
      (node (ref "C21") (pin "1") (pinfunction "1_1") (pintype "passive"))
      (node (ref "C22") (pin "1") (pinfunction "1_1") (pintype "passive"))
      (node (ref "C23") (pin "1") (pinfunction "1_1") (pintype "passive"))
      (node (ref "C24") (pin "1") (pinfunction "1_1") (pintype "passive"))
      (node (ref "C25") (pin "1") (pinfunction "1_1") (pintype "passive"))
      (node (ref "C26") (pin "1") (pinfunction "1_1") (pintype "passive"))
      (node (ref "C27") (pin "1") (pinfunction "1_1") (pintype "passive"))
      (node (ref "C28") (pin "1") (pinfunction "1_1") (pintype "passive"))
      (node (ref "C30") (pin "1") (pinfunction "1_1") (pintype "passive"))
      (node (ref "C31") (pin "1") (pinfunction "1_1") (pintype "passive"))
      (node (ref "C33") (pin "1") (pinfunction "1_1") (pintype "passive"))
      (node (ref "C34") (pin "1") (pinfunction "1_1") (pintype "passive"))
      (node (ref "C35") (pin "1") (pinfunction "1_1") (pintype "passive"))
      (node (ref "C36") (pin "1") (pinfunction "1_1") (pintype "passive"))
      (node (ref "C37") (pin "1") (pinfunction "1_1") (pintype "passive"))
      (node (ref "C38") (pin "1") (pinfunction "1_1") (pintype "passive"))
      (node (ref "C39") (pin "1") (pinfunction "1_1") (pintype "passive"))
      (node (ref "C40") (pin "1") (pinfunction "1_1") (pintype "passive"))
      (node (ref "C6") (pin "1") (pinfunction "1_1") (pintype "passive"))
      (node (ref "LED1") (pin "1-VDD") (pinfunction "VDD_1-VDD") (pintype "power_in"))
      (node (ref "LED10") (pin "1-VDD") (pinfunction "VDD_1-VDD") (pintype "power_in"))
      (node (ref "LED11") (pin "1-VDD") (pinfunction "VDD_1-VDD") (pintype "power_in"))
      (node (ref "LED12") (pin "1-VDD") (pinfunction "VDD_1-VDD") (pintype "power_in"))
      (node (ref "LED13") (pin "1-VDD") (pinfunction "VDD_1-VDD") (pintype "power_in"))
      (node (ref "LED14") (pin "1-VDD") (pinfunction "VDD_1-VDD") (pintype "power_in"))
      (node (ref "LED15") (pin "1-VDD") (pinfunction "VDD_1-VDD") (pintype "power_in"))
      (node (ref "LED16") (pin "1-VDD") (pinfunction "VDD_1-VDD") (pintype "power_in"))
      (node (ref "LED17") (pin "1-VDD") (pinfunction "VDD_1-VDD") (pintype "power_in"))
      (node (ref "LED18") (pin "1-VDD") (pinfunction "VDD_1-VDD") (pintype "power_in"))
      (node (ref "LED19") (pin "1-VDD") (pinfunction "VDD_1-VDD") (pintype "power_in"))
      (node (ref "LED2") (pin "1-VDD") (pinfunction "VDD_1-VDD") (pintype "power_in"))
      (node (ref "LED20") (pin "1-VDD") (pinfunction "VDD_1-VDD") (pintype "power_in"))
      (node (ref "LED21") (pin "1-VDD") (pinfunction "VDD_1-VDD") (pintype "power_in"))
      (node (ref "LED22") (pin "1-VDD") (pinfunction "VDD_1-VDD") (pintype "power_in"))
      (node (ref "LED23") (pin "1-VDD") (pinfunction "VDD_1-VDD") (pintype "power_in"))
      (node (ref "LED24") (pin "1-VDD") (pinfunction "VDD_1-VDD") (pintype "power_in"))
      (node (ref "LED3") (pin "1-VDD") (pinfunction "VDD_1-VDD") (pintype "power_in"))
      (node (ref "LED4") (pin "1-VDD") (pinfunction "VDD_1-VDD") (pintype "power_in"))
      (node (ref "LED5") (pin "1-VDD") (pinfunction "VDD_1-VDD") (pintype "power_in"))
      (node (ref "LED6") (pin "1-VDD") (pinfunction "VDD_1-VDD") (pintype "power_in"))
      (node (ref "LED7") (pin "1-VDD") (pinfunction "VDD_1-VDD") (pintype "power_in"))
      (node (ref "LED8") (pin "1-VDD") (pinfunction "VDD_1-VDD") (pintype "power_in"))
      (node (ref "LED9") (pin "1-VDD") (pinfunction "VDD_1-VDD") (pintype "power_in"))
      (node (ref "NEO_PIX2") (pin "1") (pinfunction "1_1") (pintype "passive"))
      (node (ref "PWR_REG") (pin "VOUT") (pinfunction "VOUT_VOUT") (pintype "bidirectional"))
      (node (ref "U$3") (pin "VIN") (pinfunction "VIN_VIN") (pintype "power_in"))
      (node (ref "U$5") (pin "13") (pinfunction "VDD_13") (pintype "bidirectional"))
      (node (ref "U$5") (pin "16") (pinfunction "PVDDR1_16") (pintype "bidirectional"))
      (node (ref "U$5") (pin "21") (pinfunction "PVDDR2_21") (pintype "bidirectional"))
      (node (ref "U$5") (pin "4") (pinfunction "PVDDL1_4") (pintype "bidirectional"))
      (node (ref "U$5") (pin "9") (pinfunction "PVDDL2_9") (pintype "bidirectional"))
    )
    (net (code "43") (name "GND") (class "Default")
      (node (ref "BT2") (pin "GND@1") (pinfunction "-_GND@1") (pintype "power_in"))
      (node (ref "C1") (pin "-") (pinfunction "-_-") (pintype "passive"))
      (node (ref "C10") (pin "2") (pinfunction "2_2") (pintype "passive"))
      (node (ref "C11") (pin "2") (pinfunction "2_2") (pintype "passive"))
      (node (ref "C12") (pin "2") (pinfunction "2_2") (pintype "passive"))
      (node (ref "C13") (pin "2") (pinfunction "2_2") (pintype "passive"))
      (node (ref "C14") (pin "2") (pinfunction "2_2") (pintype "passive"))
      (node (ref "C15") (pin "2") (pinfunction "2_2") (pintype "passive"))
      (node (ref "C16") (pin "2") (pinfunction "2_2") (pintype "passive"))
      (node (ref "C17") (pin "2") (pinfunction "2_2") (pintype "passive"))
      (node (ref "C18") (pin "2") (pinfunction "2_2") (pintype "passive"))
      (node (ref "C19") (pin "2") (pinfunction "2_2") (pintype "passive"))
      (node (ref "C2") (pin "-") (pinfunction "-_-") (pintype "passive"))
      (node (ref "C20") (pin "2") (pinfunction "2_2") (pintype "passive"))
      (node (ref "C21") (pin "2") (pinfunction "2_2") (pintype "passive"))
      (node (ref "C22") (pin "2") (pinfunction "2_2") (pintype "passive"))
      (node (ref "C23") (pin "2") (pinfunction "2_2") (pintype "passive"))
      (node (ref "C24") (pin "2") (pinfunction "2_2") (pintype "passive"))
      (node (ref "C25") (pin "2") (pinfunction "2_2") (pintype "passive"))
      (node (ref "C26") (pin "2") (pinfunction "2_2") (pintype "passive"))
      (node (ref "C27") (pin "2") (pinfunction "2_2") (pintype "passive"))
      (node (ref "C28") (pin "2") (pinfunction "2_2") (pintype "passive"))
      (node (ref "C30") (pin "2") (pinfunction "2_2") (pintype "passive"))
      (node (ref "C31") (pin "2") (pinfunction "2_2") (pintype "passive"))
      (node (ref "C32") (pin "2") (pinfunction "2_2") (pintype "passive"))
      (node (ref "C33") (pin "2") (pinfunction "2_2") (pintype "passive"))
      (node (ref "C34") (pin "2") (pinfunction "2_2") (pintype "passive"))
      (node (ref "C35") (pin "2") (pinfunction "2_2") (pintype "passive"))
      (node (ref "C36") (pin "2") (pinfunction "2_2") (pintype "passive"))
      (node (ref "C37") (pin "2") (pinfunction "2_2") (pintype "passive"))
      (node (ref "C38") (pin "2") (pinfunction "2_2") (pintype "passive"))
      (node (ref "C39") (pin "2") (pinfunction "2_2") (pintype "passive"))
      (node (ref "C40") (pin "2") (pinfunction "2_2") (pintype "passive"))
      (node (ref "C48") (pin "2") (pinfunction "2_2") (pintype "passive"))
      (node (ref "C49") (pin "2") (pinfunction "2_2") (pintype "passive"))
      (node (ref "C5") (pin "2") (pinfunction "2_2") (pintype "passive"))
      (node (ref "C50") (pin "2") (pinfunction "2_2") (pintype "passive"))
      (node (ref "C57") (pin "2") (pinfunction "2_2") (pintype "passive"))
      (node (ref "C58") (pin "2") (pinfunction "2_2") (pintype "passive"))
      (node (ref "C59") (pin "2") (pinfunction "2_2") (pintype "passive"))
      (node (ref "C6") (pin "2") (pinfunction "2_2") (pintype "passive"))
      (node (ref "C60") (pin "2") (pinfunction "2_2") (pintype "passive"))
      (node (ref "C7") (pin "2") (pinfunction "2_2") (pintype "passive"))
      (node (ref "C8") (pin "2") (pinfunction "2_2") (pintype "passive"))
      (node (ref "C9") (pin "2") (pinfunction "2_2") (pintype "passive"))
      (node (ref "FERRITE2") (pin "1") (pinfunction "1_1") (pintype "passive"))
      (node (ref "J7") (pin "6") (pinfunction "VSS_6") (pintype "passive"))
      (node (ref "J7") (pin "S1") (pinfunction "GND_S1") (pintype "passive"))
      (node (ref "J7") (pin "S2") (pinfunction "GND_S2") (pintype "passive"))
      (node (ref "J7") (pin "S3") (pinfunction "GND_S3") (pintype "passive"))
      (node (ref "J7") (pin "S5") (pinfunction "GND_S5") (pintype "passive"))
      (node (ref "LED1") (pin "3-GND") (pinfunction "GND_3-GND") (pintype "power_in"))
      (node (ref "LED10") (pin "3-GND") (pinfunction "GND_3-GND") (pintype "power_in"))
      (node (ref "LED11") (pin "3-GND") (pinfunction "GND_3-GND") (pintype "power_in"))
      (node (ref "LED12") (pin "3-GND") (pinfunction "GND_3-GND") (pintype "power_in"))
      (node (ref "LED13") (pin "3-GND") (pinfunction "GND_3-GND") (pintype "power_in"))
      (node (ref "LED14") (pin "3-GND") (pinfunction "GND_3-GND") (pintype "power_in"))
      (node (ref "LED15") (pin "3-GND") (pinfunction "GND_3-GND") (pintype "power_in"))
      (node (ref "LED16") (pin "3-GND") (pinfunction "GND_3-GND") (pintype "power_in"))
      (node (ref "LED17") (pin "3-GND") (pinfunction "GND_3-GND") (pintype "power_in"))
      (node (ref "LED18") (pin "3-GND") (pinfunction "GND_3-GND") (pintype "power_in"))
      (node (ref "LED19") (pin "3-GND") (pinfunction "GND_3-GND") (pintype "power_in"))
      (node (ref "LED2") (pin "3-GND") (pinfunction "GND_3-GND") (pintype "power_in"))
      (node (ref "LED20") (pin "3-GND") (pinfunction "GND_3-GND") (pintype "power_in"))
      (node (ref "LED21") (pin "3-GND") (pinfunction "GND_3-GND") (pintype "power_in"))
      (node (ref "LED22") (pin "3-GND") (pinfunction "GND_3-GND") (pintype "power_in"))
      (node (ref "LED23") (pin "3-GND") (pinfunction "GND_3-GND") (pintype "power_in"))
      (node (ref "LED24") (pin "3-GND") (pinfunction "GND_3-GND") (pintype "power_in"))
      (node (ref "LED3") (pin "3-GND") (pinfunction "GND_3-GND") (pintype "power_in"))
      (node (ref "LED4") (pin "3-GND") (pinfunction "GND_3-GND") (pintype "power_in"))
      (node (ref "LED5") (pin "3-GND") (pinfunction "GND_3-GND") (pintype "power_in"))
      (node (ref "LED6") (pin "3-GND") (pinfunction "GND_3-GND") (pintype "power_in"))
      (node (ref "LED7") (pin "3-GND") (pinfunction "GND_3-GND") (pintype "power_in"))
      (node (ref "LED8") (pin "3-GND") (pinfunction "GND_3-GND") (pintype "power_in"))
      (node (ref "LED9") (pin "3-GND") (pinfunction "GND_3-GND") (pintype "power_in"))
      (node (ref "MEMS1") (pin "2") (pinfunction "SELECT_2") (pintype "input"))
      (node (ref "MEMS1") (pin "P$1") (pinfunction "GND_P$1") (pintype "power_in"))
      (node (ref "NEO_PIX2") (pin "3") (pinfunction "3_3") (pintype "passive"))
      (node (ref "PWR_REG") (pin "GND") (pinfunction "GND_GND") (pintype "bidirectional"))
      (node (ref "S1") (pin "1") (pinfunction "1_1") (pintype "passive"))
      (node (ref "S1") (pin "2") (pinfunction "2_2") (pintype "passive"))
      (node (ref "S1") (pin "3") (pinfunction "3_3") (pintype "passive"))
      (node (ref "S1") (pin "4") (pinfunction "4_4") (pintype "passive"))
      (node (ref "S1") (pin "5") (pinfunction "5_5") (pintype "passive"))
      (node (ref "S1") (pin "6") (pinfunction "6_6") (pintype "passive"))
      (node (ref "S1") (pin "7") (pinfunction "7_7") (pintype "passive"))
      (node (ref "S1") (pin "8") (pinfunction "8_8") (pintype "passive"))
      (node (ref "S2") (pin "1") (pinfunction "O_1") (pintype "passive"))
      (node (ref "U$3") (pin "GND") (pinfunction "GND_GND") (pintype "power_in"))
      (node (ref "U$5") (pin "18") (pinfunction "PGNDR1_18") (pintype "bidirectional"))
      (node (ref "U$5") (pin "19") (pinfunction "PGNDR2_19") (pintype "bidirectional"))
      (node (ref "U$5") (pin "6") (pinfunction "PGNDL1_6") (pintype "bidirectional"))
      (node (ref "U$5") (pin "7") (pinfunction "PGNDL2_7") (pintype "bidirectional"))
      (node (ref "U$8") (pin "CTRL_ADR0_CS") (pinfunction "ADDR_CTRL_ADR0_CS") (pintype "bidirectional"))
      (node (ref "U$8") (pin "CTRL_MODE") (pinfunction "MODE_CTRL_MODE") (pintype "bidirectional"))
      (node (ref "U$8") (pin "GND1") (pinfunction "GND1_GND1") (pintype "bidirectional"))
      (node (ref "U$8") (pin "GND2") (pinfunction "GND2_GND2") (pintype "bidirectional"))
      (node (ref "U$8") (pin "GND3") (pinfunction "GND3_GND3") (pintype "bidirectional"))
      (node (ref "U$9") (pin "3") (pinfunction "GND_3") (pintype "bidirectional"))
      (node (ref "U2") (pin "4") (pinfunction "VSS_4") (pintype "bidirectional"))
      (node (ref "U2") (pin "5") (pinfunction "VSS_5") (pintype "bidirectional"))
      (node (ref "VEML1") (pin "3") (pinfunction "GND_3") (pintype "bidirectional"))
      (node (ref "VMEL1") (pin "1") (pinfunction "GND_1") (pintype "power_in"))
      (node (ref "VMEL1") (pin "4") (pinfunction "ADDR_4") (pintype "bidirectional"))
    )
    (net (code "44") (name "Net-(BT1--)") (class "Default")
      (node (ref "BT1") (pin "GND@1") (pinfunction "-_GND@1") (pintype "power_in"))
      (node (ref "BT2") (pin "PWR@1") (pinfunction "+_PWR@1") (pintype "power_in"))
    )
    (net (code "45") (name "Net-(C48-Pad1)") (class "Default")
      (node (ref "C48") (pin "1") (pinfunction "1_1") (pintype "passive"))
      (node (ref "C49") (pin "1") (pinfunction "1_1") (pintype "passive"))
      (node (ref "FERRITE1") (pin "2") (pinfunction "2_2") (pintype "passive"))
      (node (ref "U$8") (pin "VDDD") (pinfunction "VDDD_VDDD") (pintype "bidirectional"))
      (node (ref "U$8") (pin "VDDIO") (pinfunction "VDDIO_VDDIO") (pintype "bidirectional"))
    )
    (net (code "46") (name "Net-(C57-Pad1)") (class "Default")
      (node (ref "C57") (pin "1") (pinfunction "1_1") (pintype "passive"))
      (node (ref "U$8") (pin "VAG") (pinfunction "VAG_VAG") (pintype "bidirectional"))
    )
    (net (code "47") (name "Net-(J1-Pad2)") (class "Default")
      (node (ref "J1") (pin "2") (pinfunction "2_2") (pintype "passive"))
      (node (ref "MIC1") (pin "1") (pinfunction "1_1") (pintype "passive"))
    )
    (net (code "48") (name "Net-(J2-Pad2)") (class "Default")
      (node (ref "J2") (pin "2") (pinfunction "2_2") (pintype "passive"))
      (node (ref "MIC2") (pin "1") (pinfunction "1_1") (pintype "passive"))
    )
    (net (code "49") (name "Net-(J3-Pad2)") (class "Default")
      (node (ref "J3") (pin "2") (pinfunction "2_2") (pintype "passive"))
      (node (ref "MIC3") (pin "1") (pinfunction "1_1") (pintype "passive"))
    )
    (net (code "50") (name "Net-(J4-Pad2)") (class "Default")
      (node (ref "J4") (pin "2") (pinfunction "2_2") (pintype "passive"))
      (node (ref "MIC4") (pin "1") (pinfunction "1_1") (pintype "passive"))
    )
    (net (code "51") (name "Net-(J5-Pad2)") (class "Default")
      (node (ref "J5") (pin "2") (pinfunction "2_2") (pintype "passive"))
      (node (ref "MIC5") (pin "1") (pinfunction "1_1") (pintype "passive"))
    )
    (net (code "52") (name "Net-(J6-Pad2)") (class "Default")
      (node (ref "J6") (pin "2") (pinfunction "2_2") (pintype "passive"))
      (node (ref "MIC1") (pin "2") (pinfunction "2_2") (pintype "passive"))
    )
    (net (code "53") (name "Net-(J8-Pad2)") (class "Default")
      (node (ref "J8") (pin "2") (pinfunction "2_2") (pintype "passive"))
      (node (ref "MIC2") (pin "2") (pinfunction "2_2") (pintype "passive"))
    )
    (net (code "54") (name "Net-(J9-Pad2)") (class "Default")
      (node (ref "J9") (pin "2") (pinfunction "2_2") (pintype "passive"))
      (node (ref "MIC3") (pin "2") (pinfunction "2_2") (pintype "passive"))
    )
    (net (code "55") (name "Net-(J10-Pad2)") (class "Default")
      (node (ref "J10") (pin "2") (pinfunction "2_2") (pintype "passive"))
      (node (ref "MIC4") (pin "2") (pinfunction "2_2") (pintype "passive"))
    )
    (net (code "56") (name "Net-(J11-Pad2)") (class "Default")
      (node (ref "J11") (pin "2") (pinfunction "2_2") (pintype "passive"))
      (node (ref "MIC5") (pin "2") (pinfunction "2_2") (pintype "passive"))
    )
    (net (code "57") (name "Net-(LED1-DO)") (class "Default")
      (node (ref "LED1") (pin "2-DOUT") (pinfunction "DO_2-DOUT") (pintype "output"))
      (node (ref "LED2") (pin "4-DIN") (pinfunction "DI_4-DIN") (pintype "input"))
    )
    (net (code "58") (name "Net-(LED2-DO)") (class "Default")
      (node (ref "LED2") (pin "2-DOUT") (pinfunction "DO_2-DOUT") (pintype "output"))
      (node (ref "LED3") (pin "4-DIN") (pinfunction "DI_4-DIN") (pintype "input"))
    )
    (net (code "59") (name "Net-(LED3-DO)") (class "Default")
      (node (ref "LED3") (pin "2-DOUT") (pinfunction "DO_2-DOUT") (pintype "output"))
      (node (ref "LED4") (pin "4-DIN") (pinfunction "DI_4-DIN") (pintype "input"))
    )
    (net (code "60") (name "Net-(LED4-DO)") (class "Default")
      (node (ref "LED4") (pin "2-DOUT") (pinfunction "DO_2-DOUT") (pintype "output"))
      (node (ref "LED5") (pin "4-DIN") (pinfunction "DI_4-DIN") (pintype "input"))
    )
    (net (code "61") (name "Net-(LED5-DO)") (class "Default")
      (node (ref "LED5") (pin "2-DOUT") (pinfunction "DO_2-DOUT") (pintype "output"))
      (node (ref "LED6") (pin "4-DIN") (pinfunction "DI_4-DIN") (pintype "input"))
    )
    (net (code "62") (name "Net-(LED6-DO)") (class "Default")
      (node (ref "LED6") (pin "2-DOUT") (pinfunction "DO_2-DOUT") (pintype "output"))
      (node (ref "LED7") (pin "4-DIN") (pinfunction "DI_4-DIN") (pintype "input"))
    )
    (net (code "63") (name "Net-(LED7-DO)") (class "Default")
      (node (ref "LED7") (pin "2-DOUT") (pinfunction "DO_2-DOUT") (pintype "output"))
      (node (ref "LED8") (pin "4-DIN") (pinfunction "DI_4-DIN") (pintype "input"))
    )
    (net (code "64") (name "Net-(LED8-DO)") (class "Default")
      (node (ref "LED8") (pin "2-DOUT") (pinfunction "DO_2-DOUT") (pintype "output"))
      (node (ref "LED9") (pin "4-DIN") (pinfunction "DI_4-DIN") (pintype "input"))
    )
    (net (code "65") (name "Net-(LED10-DI)") (class "Default")
      (node (ref "LED10") (pin "4-DIN") (pinfunction "DI_4-DIN") (pintype "input"))
      (node (ref "LED9") (pin "2-DOUT") (pinfunction "DO_2-DOUT") (pintype "output"))
    )
    (net (code "66") (name "Net-(LED10-DO)") (class "Default")
      (node (ref "LED10") (pin "2-DOUT") (pinfunction "DO_2-DOUT") (pintype "output"))
      (node (ref "LED11") (pin "4-DIN") (pinfunction "DI_4-DIN") (pintype "input"))
    )
    (net (code "67") (name "Net-(LED11-DO)") (class "Default")
      (node (ref "LED11") (pin "2-DOUT") (pinfunction "DO_2-DOUT") (pintype "output"))
      (node (ref "LED12") (pin "4-DIN") (pinfunction "DI_4-DIN") (pintype "input"))
    )
    (net (code "68") (name "Net-(LED12-DO)") (class "Default")
      (node (ref "LED12") (pin "2-DOUT") (pinfunction "DO_2-DOUT") (pintype "output"))
      (node (ref "LED13") (pin "4-DIN") (pinfunction "DI_4-DIN") (pintype "input"))
    )
    (net (code "69") (name "Net-(LED13-DO)") (class "Default")
      (node (ref "LED13") (pin "2-DOUT") (pinfunction "DO_2-DOUT") (pintype "output"))
      (node (ref "LED14") (pin "4-DIN") (pinfunction "DI_4-DIN") (pintype "input"))
    )
    (net (code "70") (name "Net-(LED14-DO)") (class "Default")
      (node (ref "LED14") (pin "2-DOUT") (pinfunction "DO_2-DOUT") (pintype "output"))
      (node (ref "LED15") (pin "4-DIN") (pinfunction "DI_4-DIN") (pintype "input"))
    )
    (net (code "71") (name "Net-(LED15-DO)") (class "Default")
      (node (ref "LED15") (pin "2-DOUT") (pinfunction "DO_2-DOUT") (pintype "output"))
      (node (ref "LED16") (pin "4-DIN") (pinfunction "DI_4-DIN") (pintype "input"))
    )
    (net (code "72") (name "Net-(LED17-DO)") (class "Default")
      (node (ref "LED17") (pin "2-DOUT") (pinfunction "DO_2-DOUT") (pintype "output"))
      (node (ref "LED18") (pin "4-DIN") (pinfunction "DI_4-DIN") (pintype "input"))
    )
    (net (code "73") (name "Net-(LED18-DO)") (class "Default")
      (node (ref "LED18") (pin "2-DOUT") (pinfunction "DO_2-DOUT") (pintype "output"))
      (node (ref "LED19") (pin "4-DIN") (pinfunction "DI_4-DIN") (pintype "input"))
    )
    (net (code "74") (name "Net-(LED19-DO)") (class "Default")
      (node (ref "LED19") (pin "2-DOUT") (pinfunction "DO_2-DOUT") (pintype "output"))
      (node (ref "LED20") (pin "4-DIN") (pinfunction "DI_4-DIN") (pintype "input"))
    )
    (net (code "75") (name "Net-(LED20-DO)") (class "Default")
      (node (ref "LED20") (pin "2-DOUT") (pinfunction "DO_2-DOUT") (pintype "output"))
      (node (ref "LED21") (pin "4-DIN") (pinfunction "DI_4-DIN") (pintype "input"))
    )
    (net (code "76") (name "Net-(LED21-DO)") (class "Default")
      (node (ref "LED21") (pin "2-DOUT") (pinfunction "DO_2-DOUT") (pintype "output"))
      (node (ref "LED22") (pin "4-DIN") (pinfunction "DI_4-DIN") (pintype "input"))
    )
    (net (code "77") (name "Net-(LED22-DO)") (class "Default")
      (node (ref "LED22") (pin "2-DOUT") (pinfunction "DO_2-DOUT") (pintype "output"))
      (node (ref "LED23") (pin "4-DIN") (pinfunction "DI_4-DIN") (pintype "input"))
    )
    (net (code "78") (name "Net-(LED23-DO)") (class "Default")
      (node (ref "LED23") (pin "2-DOUT") (pinfunction "DO_2-DOUT") (pintype "output"))
      (node (ref "LED24") (pin "4-DIN") (pinfunction "DI_4-DIN") (pintype "input"))
    )
    (net (code "79") (name "Net-(MEMS1-DATA_OUT)") (class "Default")
      (node (ref "MEMS1") (pin "6") (pinfunction "DATA_OUT_6") (pintype "output"))
      (node (ref "R2") (pin "1") (pinfunction "1_1") (pintype "passive"))
    )
    (net (code "80") (name "Net-(S2-P)") (class "Default")
      (node (ref "PWR_REG") (pin "EN") (pinfunction "EN_EN") (pintype "bidirectional"))
      (node (ref "S2") (pin "2") (pinfunction "P_2") (pintype "passive"))
    )
    (net (code "81") (name "Net-(U$8-LINEOUTL)") (class "Default")
      (node (ref "C54") (pin "1") (pinfunction "1_1") (pintype "passive"))
      (node (ref "U$8") (pin "LINEOUT_L") (pinfunction "LINEOUTL_LINEOUT_L") (pintype "bidirectional"))
    )
    (net (code "82") (name "Net-(U$8-LINEOUTR)") (class "Default")
      (node (ref "C53") (pin "1") (pinfunction "1_1") (pintype "passive"))
      (node (ref "U$8") (pin "LINEOUT_R") (pinfunction "LINEOUTR_LINEOUT_R") (pintype "bidirectional"))
    )
    (net (code "83") (name "Net-(U$8-MCLK)") (class "Default")
      (node (ref "R9") (pin "2") (pinfunction "2_2") (pintype "passive"))
      (node (ref "U$8") (pin "SYS_MCLK") (pinfunction "MCLK_SYS_MCLK") (pintype "bidirectional"))
    )
    (net (code "84") (name "Net-(U$8-RX)") (class "Default")
      (node (ref "DIN") (pin "2") (pinfunction "2_2") (pintype "passive"))
      (node (ref "U$8") (pin "I2S_DIN") (pinfunction "RX_I2S_DIN") (pintype "bidirectional"))
    )
    (net (code "85") (name "Net-(U$8-TX)") (class "Default")
      (node (ref "DOUT") (pin "2") (pinfunction "2_2") (pintype "passive"))
      (node (ref "U$8") (pin "I2S_DOUT") (pinfunction "TX_I2S_DOUT") (pintype "bidirectional"))
    )
    (net (code "86") (name "Net-(U$9-OUT)") (class "Default")
      (node (ref "C50") (pin "1") (pinfunction "1_1") (pintype "passive"))
      (node (ref "U$8") (pin "VDDA") (pinfunction "VDDA_VDDA") (pintype "bidirectional"))
      (node (ref "U$9") (pin "2") (pinfunction "OUT_2") (pintype "bidirectional"))
    )
    (net (code "87") (name "Net-(VEML1-VDD)") (class "Default")
      (node (ref "C10") (pin "1") (pinfunction "1_1") (pintype "passive"))
      (node (ref "C8") (pin "1") (pinfunction "1_1") (pintype "passive"))
      (node (ref "R1") (pin "1") (pinfunction "1_1") (pintype "passive"))
      (node (ref "VEML1") (pin "2") (pinfunction "VDD_2") (pintype "bidirectional"))
      (node (ref "VMEL1") (pin "6") (pinfunction "VDD_6") (pintype "power_in"))
    )
    (net (code "88") (name "unconnected-(J7-CD_SW-Pad9)") (class "Default")
      (node (ref "J7") (pin "9") (pinfunction "CD_SW_9") (pintype "passive"))
    )
    (net (code "89") (name "unconnected-(J7-DAT1-Pad8)") (class "Default")
      (node (ref "J7") (pin "8") (pinfunction "DAT1_8") (pintype "passive"))
    )
    (net (code "90") (name "unconnected-(J7-DAT2-Pad1)") (class "Default")
      (node (ref "J7") (pin "1") (pinfunction "DAT2_1") (pintype "passive"))
    )
    (net (code "91") (name "unconnected-(LED24-DO-Pad2-DOUT)") (class "Default")
      (node (ref "LED24") (pin "2-DOUT") (pinfunction "DO_2-DOUT") (pintype "output"))
    )
    (net (code "92") (name "unconnected-(PWR_REG-PadPG)") (class "Default")
      (node (ref "PWR_REG") (pin "PG") (pinfunction "PG_PG") (pintype "bidirectional"))
    )
    (net (code "93") (name "unconnected-(PWR_REG-PadSEL)") (class "Default")
      (node (ref "PWR_REG") (pin "SEL") (pinfunction "SEL_SEL") (pintype "bidirectional"))
    )
    (net (code "94") (name "unconnected-(S2-S-Pad3)") (class "Default")
      (node (ref "S2") (pin "3") (pinfunction "S_3") (pintype "passive"))
    )
    (net (code "95") (name "unconnected-(U$5-NC-Pad15)") (class "Default")
      (node (ref "U$5") (pin "15") (pinfunction "NC_15") (pintype "bidirectional"))
    )
    (net (code "96") (name "unconnected-(U$8-HPL-PadHP_L)") (class "Default")
      (node (ref "U$8") (pin "HP_L") (pinfunction "HPL_HP_L") (pintype "bidirectional"))
    )
    (net (code "97") (name "unconnected-(U$8-HPR-PadHP_R)") (class "Default")
      (node (ref "U$8") (pin "HP_R") (pinfunction "HPR_HP_R") (pintype "bidirectional"))
    )
    (net (code "98") (name "unconnected-(U$8-HPVGND-PadHP_VGND)") (class "Default")
      (node (ref "U$8") (pin "HP_VGND") (pinfunction "HPVGND_HP_VGND") (pintype "bidirectional"))
    )
    (net (code "99") (name "unconnected-(U$8-LINEINL-PadLININ_L)") (class "Default")
      (node (ref "U$8") (pin "LININ_L") (pinfunction "LINEINL_LININ_L") (pintype "bidirectional"))
    )
    (net (code "100") (name "unconnected-(U$8-LINEINR-PadLININ_R)") (class "Default")
      (node (ref "U$8") (pin "LININ_R") (pinfunction "LINEINR_LININ_R") (pintype "bidirectional"))
    )
    (net (code "101") (name "unconnected-(U$8-MICBIAS-PadMIC_BIAS)") (class "Default")
      (node (ref "U$8") (pin "MIC_BIAS") (pinfunction "MICBIAS_MIC_BIAS") (pintype "bidirectional"))
    )
    (net (code "102") (name "unconnected-(U$8-PadCPFILT)") (class "Default")
      (node (ref "U$8") (pin "CPFILT") (pinfunction "CPFILT_CPFILT") (pintype "bidirectional"))
    )
    (net (code "103") (name "unconnected-(U$8-PadMIC)") (class "Default")
      (node (ref "U$8") (pin "MIC") (pinfunction "MIC_MIC") (pintype "bidirectional"))
    )
  )
)
